# 20180608-iot_eagle7.net
KiCad netlist of a schematic drawn in EAGLE
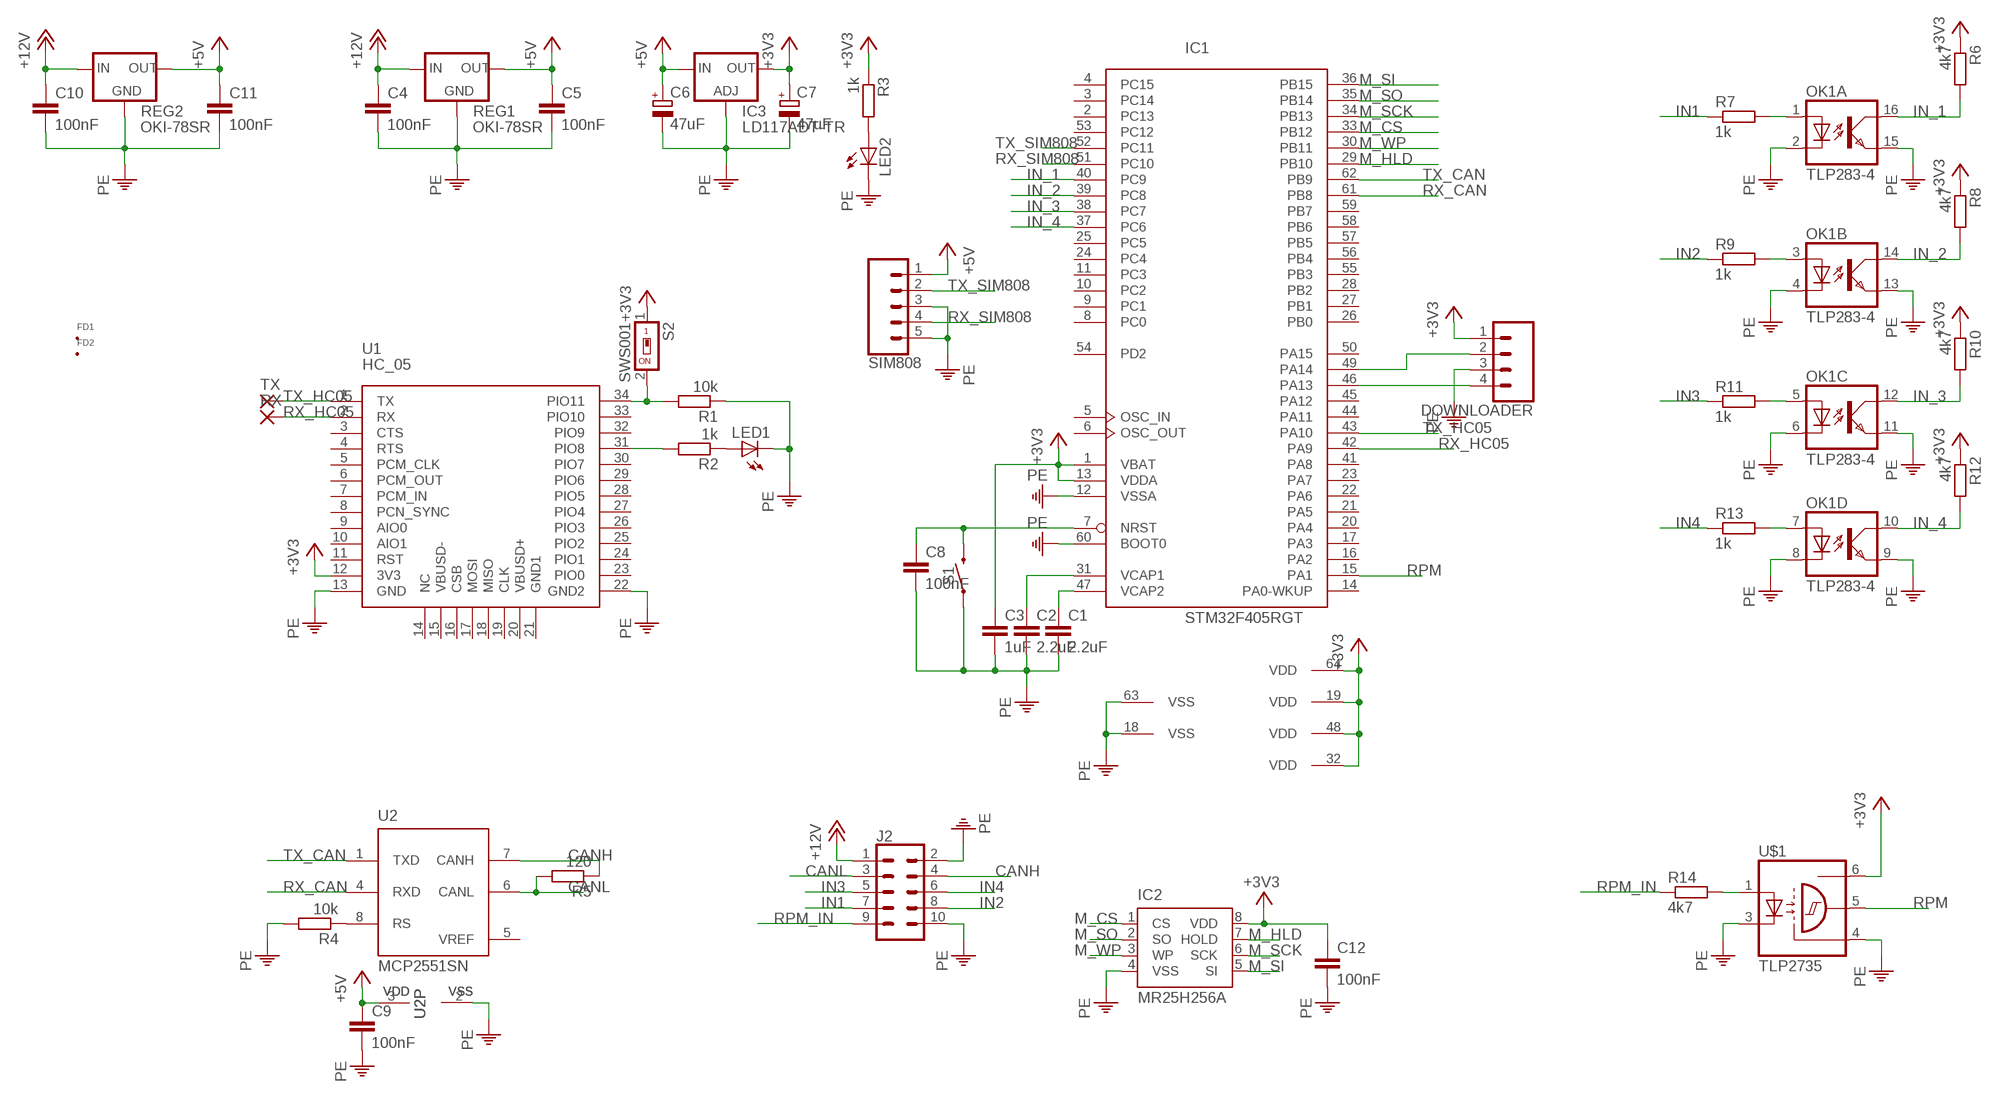
[diagram p0: schematic, sheet 1]

(export (version "E")
  (design (tool "Eeschema 10.0.6"))
  (components
    (comp (ref "C1")
      (value "2.2uF")
      (footprint "eagle-import:C0805")
      (libsource (lib "eagle-import") (part "C-EUC0805"))
    )
    (comp (ref "C2")
      (value "2.2uF")
      (footprint "eagle-import:C0805")
      (libsource (lib "eagle-import") (part "C-EUC0805"))
    )
    (comp (ref "C3")
      (value "1uF")
      (footprint "eagle-import:C0805")
      (libsource (lib "eagle-import") (part "C-EUC0805"))
    )
    (comp (ref "C4")
      (value "100nF")
      (footprint "eagle-import:C0805")
      (libsource (lib "eagle-import") (part "C-EUC0805"))
    )
    (comp (ref "C5")
      (value "100nF")
      (footprint "eagle-import:C0805")
      (libsource (lib "eagle-import") (part "C-EUC0805"))
    )
    (comp (ref "C6")
      (value "47uF")
      (footprint "eagle-import:CT7343")
      (libsource (lib "eagle-import") (part "CPOL-EUCT7343"))
    )
    (comp (ref "C7")
      (value "47uF")
      (footprint "eagle-import:CT7343")
      (libsource (lib "eagle-import") (part "CPOL-EUCT7343"))
    )
    (comp (ref "C8")
      (value "100nF")
      (footprint "eagle-import:C0805")
      (libsource (lib "eagle-import") (part "C-EUC0805"))
    )
    (comp (ref "C9")
      (value "100nF")
      (footprint "eagle-import:C0805")
      (libsource (lib "eagle-import") (part "C-EUC0805"))
    )
    (comp (ref "C10")
      (value "100nF")
      (footprint "eagle-import:C0805")
      (libsource (lib "eagle-import") (part "C-EUC0805"))
    )
    (comp (ref "C11")
      (value "100nF")
      (footprint "eagle-import:C0805")
      (libsource (lib "eagle-import") (part "C-EUC0805"))
    )
    (comp (ref "C12")
      (value "100nF")
      (footprint "eagle-import:C0805")
      (libsource (lib "eagle-import") (part "C-EUC0805"))
    )
    (comp (ref "DOWNLOADER")
      (value "CONN_04")
      (footprint "eagle-import:1X04")
      (libsource (lib "eagle-import") (part "CONN_04"))
    )
    (comp (ref "FD1")
      (value "FID_40MIL")
      (footprint "eagle-import:FID_040")
      (libsource (lib "eagle-import") (part "FID_40MIL"))
    )
    (comp (ref "FD2")
      (value "FID_40MIL")
      (footprint "eagle-import:FID_040")
      (libsource (lib "eagle-import") (part "FID_40MIL"))
    )
    (comp (ref "IC1")
      (value "STM32F405RGT")
      (footprint "eagle-import:LQFP64")
      (fields (field (name "SPICEPREFIX") "X"))
      (libsource (lib "eagle-import") (part "STM32F405RTG"))
    )
    (comp (ref "IC2")
      (value "MR25H256A")
      (footprint "eagle-import:SON127P600X500X90-9T210")
      (libsource (lib "eagle-import") (part "MR25H256A"))
    )
    (comp (ref "IC3")
      (value "LD117ADT-TR")
      (footprint "eagle-import:DPACK")
      (libsource (lib "eagle-import") (part "LD117A?DT-TR"))
    )
    (comp (ref "J2")
      (value "CONN_05X2")
      (footprint "eagle-import:2X5-EDGE_SMD")
      (libsource (lib "eagle-import") (part "CONN_05X2"))
    )
    (comp (ref "LED1")
      (value "LEDCHIP-LED0805")
      (footprint "eagle-import:CHIP-LED0805")
      (libsource (lib "eagle-import") (part "LEDCHIP-LED0805"))
    )
    (comp (ref "LED2")
      (value "LEDCHIP-LED0805")
      (footprint "eagle-import:CHIP-LED0805")
      (libsource (lib "eagle-import") (part "LEDCHIP-LED0805"))
    )
    (comp (ref "OK1")
      (value "TLP283-4")
      (footprint "eagle-import:MINI-FLAT-16")
      (libsource (lib "eagle-import") (part "TLP283-4"))
    )
    (comp (ref "R1")
      (value "10k")
      (footprint "eagle-import:R0805")
      (libsource (lib "eagle-import") (part "R-EU_R0805"))
    )
    (comp (ref "R2")
      (value "1k")
      (footprint "eagle-import:R0805")
      (libsource (lib "eagle-import") (part "R-EU_R0805"))
    )
    (comp (ref "R3")
      (value "1k")
      (footprint "eagle-import:R0805")
      (libsource (lib "eagle-import") (part "R-EU_R0805"))
    )
    (comp (ref "R4")
      (value "10k")
      (footprint "eagle-import:R0805")
      (libsource (lib "eagle-import") (part "R-EU_R0805"))
    )
    (comp (ref "R5")
      (value "120")
      (footprint "eagle-import:R0805")
      (libsource (lib "eagle-import") (part "R-EU_R0805"))
    )
    (comp (ref "R6")
      (value "4k7")
      (footprint "eagle-import:R0805")
      (libsource (lib "eagle-import") (part "R-EU_R0805"))
    )
    (comp (ref "R7")
      (value "1k")
      (footprint "eagle-import:R0805")
      (libsource (lib "eagle-import") (part "R-EU_R0805"))
    )
    (comp (ref "R8")
      (value "4k7")
      (footprint "eagle-import:R0805")
      (libsource (lib "eagle-import") (part "R-EU_R0805"))
    )
    (comp (ref "R9")
      (value "1k")
      (footprint "eagle-import:R0805")
      (libsource (lib "eagle-import") (part "R-EU_R0805"))
    )
    (comp (ref "R10")
      (value "4k7")
      (footprint "eagle-import:R0805")
      (libsource (lib "eagle-import") (part "R-EU_R0805"))
    )
    (comp (ref "R11")
      (value "1k")
      (footprint "eagle-import:R0805")
      (libsource (lib "eagle-import") (part "R-EU_R0805"))
    )
    (comp (ref "R12")
      (value "4k7")
      (footprint "eagle-import:R0805")
      (libsource (lib "eagle-import") (part "R-EU_R0805"))
    )
    (comp (ref "R13")
      (value "1k")
      (footprint "eagle-import:R0805")
      (libsource (lib "eagle-import") (part "R-EU_R0805"))
    )
    (comp (ref "R14")
      (value "4k7")
      (footprint "eagle-import:R0805")
      (libsource (lib "eagle-import") (part "R-EU_R0805"))
    )
    (comp (ref "REG1")
      (value "OKI-78SR")
      (footprint "eagle-import:HDRV3W64P254_1X3_1195X508X838B")
      (libsource (lib "eagle-import") (part "OKI-78SR"))
    )
    (comp (ref "REG2")
      (value "OKI-78SR")
      (footprint "eagle-import:HDRV3W64P254_1X3_1195X508X838B")
      (libsource (lib "eagle-import") (part "OKI-78SR"))
    )
    (comp (ref "RX")
      (value "SMD2")
      (footprint "eagle-import:SMD1,27-2,54")
      (libsource (lib "eagle-import") (part "SMD2"))
    )
    (comp (ref "S1")
      (value "MOMENTARY-SWITCH-SPST-SMD-6.0X3.5MM")
      (footprint "eagle-import:TACTILE_SWITCH_SMD_6.0X3.5MM")
      (libsource (lib "eagle-import") (part "MOMENTARY-SWITCH-SPST-SMD-6.0X3.5MM"))
    )
    (comp (ref "S2")
      (value "SWS001")
      (footprint "eagle-import:SMS-001")
      (libsource (lib "eagle-import") (part "SWS001"))
    )
    (comp (ref "SIM808")
      (value "CONN_05")
      (footprint "eagle-import:1X05")
      (libsource (lib "eagle-import") (part "CONN_05"))
    )
    (comp (ref "TX")
      (value "SMD2")
      (footprint "eagle-import:SMD1,27-2,54")
      (libsource (lib "eagle-import") (part "SMD2"))
    )
    (comp (ref "U$1")
      (value "TLP2735")
      (footprint "eagle-import:SOIC127P1000X210-6")
      (libsource (lib "eagle-import") (part "TLP2735"))
    )
    (comp (ref "U1")
      (value "HC_05")
      (footprint "eagle-import:BLUETOOTH_SMD")
      (libsource (lib "eagle-import") (part "HC_05"))
    )
    (comp (ref "U2")
      (value "MCP2551SN")
      (footprint "eagle-import:SO-08")
      (fields (field (name "SPICEPREFIX") "X"))
      (libsource (lib "eagle-import") (part "MCP2551SN"))
    )
  )
  (nets
    (net (code "1") (name "+3V3") (class "Default")
      (node (ref "C12") (pin "1") (pinfunction "1_1") (pintype "passive"))
      (node (ref "C3") (pin "1") (pinfunction "1_1") (pintype "passive"))
      (node (ref "C7") (pin "+") (pinfunction "+_+") (pintype "passive"))
      (node (ref "DOWNLOADER") (pin "1") (pinfunction "1_1") (pintype "passive"))
      (node (ref "IC1") (pin "1") (pinfunction "VBAT_1") (pintype "power_in"))
      (node (ref "IC1") (pin "13") (pinfunction "VDDA_13") (pintype "power_in"))
      (node (ref "IC1") (pin "19") (pinfunction "VDD_19") (pintype "power_in"))
      (node (ref "IC1") (pin "32") (pinfunction "VDD_32") (pintype "power_in"))
      (node (ref "IC1") (pin "48") (pinfunction "VDD_48") (pintype "power_in"))
      (node (ref "IC1") (pin "64") (pinfunction "VDD_64") (pintype "power_in"))
      (node (ref "IC2") (pin "8") (pinfunction "VDD_8") (pintype "power_in"))
      (node (ref "IC3") (pin "4") (pinfunction "OUT_4") (pintype "passive"))
      (node (ref "R10") (pin "1") (pinfunction "1_1") (pintype "passive"))
      (node (ref "R12") (pin "1") (pinfunction "1_1") (pintype "passive"))
      (node (ref "R3") (pin "1") (pinfunction "1_1") (pintype "passive"))
      (node (ref "R6") (pin "1") (pinfunction "1_1") (pintype "passive"))
      (node (ref "R8") (pin "1") (pinfunction "1_1") (pintype "passive"))
      (node (ref "S2") (pin "1") (pinfunction "1_1") (pintype "passive"))
      (node (ref "U$1") (pin "6") (pinfunction "VCC_6") (pintype "passive"))
      (node (ref "U1") (pin "12") (pinfunction "3V3_12") (pintype "bidirectional"))
    )
    (net (code "2") (name "+5V") (class "Default")
      (node (ref "C11") (pin "1") (pinfunction "1_1") (pintype "passive"))
      (node (ref "C5") (pin "1") (pinfunction "1_1") (pintype "passive"))
      (node (ref "C6") (pin "+") (pinfunction "+_+") (pintype "passive"))
      (node (ref "C9") (pin "1") (pinfunction "1_1") (pintype "passive"))
      (node (ref "IC3") (pin "3") (pinfunction "IN_3") (pintype "input"))
      (node (ref "REG1") (pin "3") (pinfunction "OUT_3") (pintype "passive"))
      (node (ref "REG2") (pin "3") (pinfunction "OUT_3") (pintype "passive"))
      (node (ref "SIM808") (pin "1") (pinfunction "1_1") (pintype "passive"))
      (node (ref "U2") (pin "3") (pinfunction "VDD_3") (pintype "power_in"))
    )
    (net (code "3") (name "+12V") (class "Default")
      (node (ref "C10") (pin "1") (pinfunction "1_1") (pintype "passive"))
      (node (ref "C4") (pin "1") (pinfunction "1_1") (pintype "passive"))
      (node (ref "J2") (pin "1") (pinfunction "1_1") (pintype "passive"))
      (node (ref "REG1") (pin "1") (pinfunction "IN_1") (pintype "input"))
      (node (ref "REG2") (pin "1") (pinfunction "IN_1") (pintype "input"))
    )
    (net (code "4") (name "/CANH") (class "Default")
      (node (ref "J2") (pin "4") (pinfunction "4_4") (pintype "passive"))
      (node (ref "R5") (pin "1") (pinfunction "1_1") (pintype "passive"))
      (node (ref "U2") (pin "7") (pinfunction "CANH_7") (pintype "bidirectional"))
    )
    (net (code "5") (name "/CANL") (class "Default")
      (node (ref "J2") (pin "3") (pinfunction "3_3") (pintype "passive"))
      (node (ref "R5") (pin "2") (pinfunction "2_2") (pintype "passive"))
      (node (ref "U2") (pin "6") (pinfunction "CANL_6") (pintype "bidirectional"))
    )
    (net (code "6") (name "/IN1") (class "Default")
      (node (ref "J2") (pin "7") (pinfunction "7_7") (pintype "passive"))
      (node (ref "R7") (pin "1") (pinfunction "1_1") (pintype "passive"))
    )
    (net (code "7") (name "/IN2") (class "Default")
      (node (ref "J2") (pin "8") (pinfunction "8_8") (pintype "passive"))
      (node (ref "R9") (pin "1") (pinfunction "1_1") (pintype "passive"))
    )
    (net (code "8") (name "/IN3") (class "Default")
      (node (ref "J2") (pin "5") (pinfunction "5_5") (pintype "passive"))
      (node (ref "R11") (pin "1") (pinfunction "1_1") (pintype "passive"))
    )
    (net (code "9") (name "/IN4") (class "Default")
      (node (ref "J2") (pin "6") (pinfunction "6_6") (pintype "passive"))
      (node (ref "R13") (pin "1") (pinfunction "1_1") (pintype "passive"))
    )
    (net (code "10") (name "/IN_1") (class "Default")
      (node (ref "IC1") (pin "40") (pinfunction "PC9_40") (pintype "bidirectional"))
      (node (ref "OK1") (pin "16") (pinfunction "COL_16") (pintype "passive"))
      (node (ref "R6") (pin "2") (pinfunction "2_2") (pintype "passive"))
    )
    (net (code "11") (name "/IN_2") (class "Default")
      (node (ref "IC1") (pin "39") (pinfunction "PC8_39") (pintype "bidirectional"))
      (node (ref "OK1") (pin "14") (pinfunction "COL_14") (pintype "passive"))
      (node (ref "R8") (pin "2") (pinfunction "2_2") (pintype "passive"))
    )
    (net (code "12") (name "/IN_3") (class "Default")
      (node (ref "IC1") (pin "38") (pinfunction "PC7_38") (pintype "bidirectional"))
      (node (ref "OK1") (pin "12") (pinfunction "COL_12") (pintype "passive"))
      (node (ref "R10") (pin "2") (pinfunction "2_2") (pintype "passive"))
    )
    (net (code "13") (name "/IN_4") (class "Default")
      (node (ref "IC1") (pin "37") (pinfunction "PC6_37") (pintype "bidirectional"))
      (node (ref "OK1") (pin "10") (pinfunction "COL_10") (pintype "passive"))
      (node (ref "R12") (pin "2") (pinfunction "2_2") (pintype "passive"))
    )
    (net (code "14") (name "/M_CS") (class "Default")
      (node (ref "IC1") (pin "33") (pinfunction "PB12_33") (pintype "bidirectional"))
      (node (ref "IC2") (pin "1") (pinfunction "CS_1") (pintype "bidirectional"))
    )
    (net (code "15") (name "/M_HLD") (class "Default")
      (node (ref "IC1") (pin "29") (pinfunction "PB10_29") (pintype "bidirectional"))
      (node (ref "IC2") (pin "7") (pinfunction "HOLD_7") (pintype "output"))
    )
    (net (code "16") (name "/M_SCK") (class "Default")
      (node (ref "IC1") (pin "34") (pinfunction "PB13_34") (pintype "bidirectional"))
      (node (ref "IC2") (pin "6") (pinfunction "SCK_6") (pintype "power_in"))
    )
    (net (code "17") (name "/M_SI") (class "Default")
      (node (ref "IC1") (pin "36") (pinfunction "PB15_36") (pintype "bidirectional"))
      (node (ref "IC2") (pin "5") (pinfunction "SI_5") (pintype "input"))
    )
    (net (code "18") (name "/M_SO") (class "Default")
      (node (ref "IC1") (pin "35") (pinfunction "PB14_35") (pintype "bidirectional"))
      (node (ref "IC2") (pin "2") (pinfunction "SO_2") (pintype "input"))
    )
    (net (code "19") (name "/M_WP") (class "Default")
      (node (ref "IC1") (pin "30") (pinfunction "PB11_30") (pintype "bidirectional"))
      (node (ref "IC2") (pin "3") (pinfunction "WP_3") (pintype "input"))
    )
    (net (code "20") (name "/RPM") (class "Default")
      (node (ref "IC1") (pin "15") (pinfunction "PA1_15") (pintype "bidirectional"))
      (node (ref "U$1") (pin "5") (pinfunction "OUT_5") (pintype "passive"))
    )
    (net (code "21") (name "/RPM_IN") (class "Default")
      (node (ref "J2") (pin "9") (pinfunction "9_9") (pintype "passive"))
      (node (ref "R14") (pin "1") (pinfunction "1_1") (pintype "passive"))
    )
    (net (code "22") (name "/RX_CAN") (class "Default")
      (node (ref "IC1") (pin "61") (pinfunction "PB8_61") (pintype "bidirectional"))
      (node (ref "U2") (pin "4") (pinfunction "RXD_4") (pintype "output"))
    )
    (net (code "23") (name "/RX_HC05") (class "Default")
      (node (ref "IC1") (pin "42") (pinfunction "PA9_42") (pintype "bidirectional"))
      (node (ref "RX") (pin "1") (pinfunction "P_1") (pintype "passive"))
      (node (ref "U1") (pin "2") (pinfunction "RX_2") (pintype "bidirectional"))
    )
    (net (code "24") (name "/RX_SIM808") (class "Default")
      (node (ref "IC1") (pin "51") (pinfunction "PC10_51") (pintype "bidirectional"))
      (node (ref "SIM808") (pin "4") (pinfunction "4_4") (pintype "passive"))
    )
    (net (code "25") (name "/TX_CAN") (class "Default")
      (node (ref "IC1") (pin "62") (pinfunction "PB9_62") (pintype "bidirectional"))
      (node (ref "U2") (pin "1") (pinfunction "TXD_1") (pintype "input"))
    )
    (net (code "26") (name "/TX_HC05") (class "Default")
      (node (ref "IC1") (pin "43") (pinfunction "PA10_43") (pintype "bidirectional"))
      (node (ref "TX") (pin "1") (pinfunction "P_1") (pintype "passive"))
      (node (ref "U1") (pin "1") (pinfunction "TX_1") (pintype "bidirectional"))
    )
    (net (code "27") (name "/TX_SIM808") (class "Default")
      (node (ref "IC1") (pin "52") (pinfunction "PC11_52") (pintype "bidirectional"))
      (node (ref "SIM808") (pin "2") (pinfunction "2_2") (pintype "passive"))
    )
    (net (code "28") (name "/VREF") (class "Default")
      (node (ref "U2") (pin "5") (pinfunction "VREF_5") (pintype "power_in"))
    )
    (net (code "29") (name "Net-(IC1A-NRST)") (class "Default")
      (node (ref "C8") (pin "1") (pinfunction "1_1") (pintype "passive"))
      (node (ref "IC1") (pin "7") (pinfunction "NRST_7") (pintype "bidirectional"))
      (node (ref "S1") (pin "2") (pinfunction "2_2") (pintype "passive"))
    )
    (net (code "30") (name "Net-(IC1A-PA13)") (class "Default")
      (node (ref "DOWNLOADER") (pin "4") (pinfunction "4_4") (pintype "passive"))
      (node (ref "IC1") (pin "46") (pinfunction "PA13_46") (pintype "bidirectional"))
    )
    (net (code "31") (name "Net-(IC1A-PA14)") (class "Default")
      (node (ref "DOWNLOADER") (pin "2") (pinfunction "2_2") (pintype "passive"))
      (node (ref "IC1") (pin "49") (pinfunction "PA14_49") (pintype "bidirectional"))
    )
    (net (code "32") (name "Net-(IC1A-VCAP1)") (class "Default")
      (node (ref "C2") (pin "1") (pinfunction "1_1") (pintype "passive"))
      (node (ref "IC1") (pin "31") (pinfunction "VCAP1_31") (pintype "power_in"))
    )
    (net (code "33") (name "Net-(IC1A-VCAP2)") (class "Default")
      (node (ref "C1") (pin "1") (pinfunction "1_1") (pintype "passive"))
      (node (ref "IC1") (pin "47") (pinfunction "VCAP2_47") (pintype "power_in"))
    )
    (net (code "34") (name "Net-(LED1-PadA)") (class "Default")
      (node (ref "LED1") (pin "A") (pinfunction "A_A") (pintype "passive"))
      (node (ref "R2") (pin "1") (pinfunction "1_1") (pintype "passive"))
    )
    (net (code "35") (name "Net-(LED2-PadA)") (class "Default")
      (node (ref "LED2") (pin "A") (pinfunction "A_A") (pintype "passive"))
      (node (ref "R3") (pin "2") (pinfunction "2_2") (pintype "passive"))
    )
    (net (code "36") (name "Net-(OK1A-A)") (class "Default")
      (node (ref "OK1") (pin "1") (pinfunction "A_1") (pintype "passive"))
      (node (ref "R7") (pin "2") (pinfunction "2_2") (pintype "passive"))
    )
    (net (code "37") (name "Net-(OK1B-A)") (class "Default")
      (node (ref "OK1") (pin "3") (pinfunction "A_3") (pintype "passive"))
      (node (ref "R9") (pin "2") (pinfunction "2_2") (pintype "passive"))
    )
    (net (code "38") (name "Net-(OK1C-A)") (class "Default")
      (node (ref "OK1") (pin "5") (pinfunction "A_5") (pintype "passive"))
      (node (ref "R11") (pin "2") (pinfunction "2_2") (pintype "passive"))
    )
    (net (code "39") (name "Net-(OK1D-A)") (class "Default")
      (node (ref "OK1") (pin "7") (pinfunction "A_7") (pintype "passive"))
      (node (ref "R13") (pin "2") (pinfunction "2_2") (pintype "passive"))
    )
    (net (code "40") (name "Net-(U$1-A)") (class "Default")
      (node (ref "R14") (pin "2") (pinfunction "2_2") (pintype "passive"))
      (node (ref "U$1") (pin "1") (pinfunction "A_1") (pintype "passive"))
    )
    (net (code "41") (name "Net-(U1-PIO8)") (class "Default")
      (node (ref "R2") (pin "2") (pinfunction "2_2") (pintype "passive"))
      (node (ref "U1") (pin "31") (pinfunction "PIO8_31") (pintype "bidirectional"))
    )
    (net (code "42") (name "Net-(U1-PIO11)") (class "Default")
      (node (ref "R1") (pin "2") (pinfunction "2_2") (pintype "passive"))
      (node (ref "S2") (pin "2") (pinfunction "2_2") (pintype "passive"))
      (node (ref "U1") (pin "34") (pinfunction "PIO11_34") (pintype "bidirectional"))
    )
    (net (code "43") (name "Net-(U2A-RS)") (class "Default")
      (node (ref "R4") (pin "1") (pinfunction "1_1") (pintype "passive"))
      (node (ref "U2") (pin "8") (pinfunction "RS_8") (pintype "input"))
    )
    (net (code "44") (name "PE") (class "Default")
      (node (ref "C1") (pin "2") (pinfunction "2_2") (pintype "passive"))
      (node (ref "C10") (pin "2") (pinfunction "2_2") (pintype "passive"))
      (node (ref "C11") (pin "2") (pinfunction "2_2") (pintype "passive"))
      (node (ref "C12") (pin "2") (pinfunction "2_2") (pintype "passive"))
      (node (ref "C2") (pin "2") (pinfunction "2_2") (pintype "passive"))
      (node (ref "C3") (pin "2") (pinfunction "2_2") (pintype "passive"))
      (node (ref "C4") (pin "2") (pinfunction "2_2") (pintype "passive"))
      (node (ref "C5") (pin "2") (pinfunction "2_2") (pintype "passive"))
      (node (ref "C6") (pin "-") (pinfunction "-_-") (pintype "passive"))
      (node (ref "C7") (pin "-") (pinfunction "-_-") (pintype "passive"))
      (node (ref "C8") (pin "2") (pinfunction "2_2") (pintype "passive"))
      (node (ref "C9") (pin "2") (pinfunction "2_2") (pintype "passive"))
      (node (ref "DOWNLOADER") (pin "3") (pinfunction "3_3") (pintype "passive"))
      (node (ref "IC1") (pin "12") (pinfunction "VSSA_12") (pintype "power_in"))
      (node (ref "IC1") (pin "18") (pinfunction "VSS_18") (pintype "power_in"))
      (node (ref "IC1") (pin "60") (pinfunction "BOOT0_60") (pintype "input"))
      (node (ref "IC1") (pin "63") (pinfunction "VSS_63") (pintype "power_in"))
      (node (ref "IC2") (pin "4") (pinfunction "VSS_4") (pintype "input"))
      (node (ref "IC3") (pin "1") (pinfunction "ADJ_1") (pintype "input"))
      (node (ref "J2") (pin "10") (pinfunction "10_10") (pintype "passive"))
      (node (ref "J2") (pin "2") (pinfunction "2_2") (pintype "passive"))
      (node (ref "LED1") (pin "C") (pinfunction "C_C") (pintype "passive"))
      (node (ref "LED2") (pin "C") (pinfunction "C_C") (pintype "passive"))
      (node (ref "OK1") (pin "11") (pinfunction "EMIT_11") (pintype "passive"))
      (node (ref "OK1") (pin "13") (pinfunction "EMIT_13") (pintype "passive"))
      (node (ref "OK1") (pin "15") (pinfunction "EMIT_15") (pintype "passive"))
      (node (ref "OK1") (pin "2") (pinfunction "C_2") (pintype "passive"))
      (node (ref "OK1") (pin "4") (pinfunction "C_4") (pintype "passive"))
      (node (ref "OK1") (pin "6") (pinfunction "C_6") (pintype "passive"))
      (node (ref "OK1") (pin "8") (pinfunction "C_8") (pintype "passive"))
      (node (ref "OK1") (pin "9") (pinfunction "EMIT_9") (pintype "passive"))
      (node (ref "R1") (pin "1") (pinfunction "1_1") (pintype "passive"))
      (node (ref "R4") (pin "2") (pinfunction "2_2") (pintype "passive"))
      (node (ref "REG1") (pin "2") (pinfunction "GND_2") (pintype "input"))
      (node (ref "REG2") (pin "2") (pinfunction "GND_2") (pintype "input"))
      (node (ref "S1") (pin "1") (pinfunction "1_1") (pintype "passive"))
      (node (ref "SIM808") (pin "3") (pinfunction "3_3") (pintype "passive"))
      (node (ref "SIM808") (pin "5") (pinfunction "5_5") (pintype "passive"))
      (node (ref "U$1") (pin "3") (pinfunction "C_3") (pintype "passive"))
      (node (ref "U$1") (pin "4") (pinfunction "GND_4") (pintype "passive"))
      (node (ref "U1") (pin "13") (pinfunction "GND_13") (pintype "bidirectional"))
      (node (ref "U1") (pin "22") (pinfunction "GND2_22") (pintype "bidirectional"))
      (node (ref "U2") (pin "2") (pinfunction "VSS_2") (pintype "power_in"))
    )
    (net (code "45") (name "unconnected-(IC1A-OSC_IN-Pad5)") (class "Default")
      (node (ref "IC1") (pin "5") (pinfunction "OSC_IN_5") (pintype "bidirectional"))
    )
    (net (code "46") (name "unconnected-(IC1A-OSC_OUT-Pad6)") (class "Default")
      (node (ref "IC1") (pin "6") (pinfunction "OSC_OUT_6") (pintype "bidirectional"))
    )
    (net (code "47") (name "unconnected-(IC1A-PA0-WKUP-Pad14)") (class "Default")
      (node (ref "IC1") (pin "14") (pinfunction "PA0-WKUP_14") (pintype "bidirectional"))
    )
    (net (code "48") (name "unconnected-(IC1A-PA2-Pad16)") (class "Default")
      (node (ref "IC1") (pin "16") (pinfunction "PA2_16") (pintype "bidirectional"))
    )
    (net (code "49") (name "unconnected-(IC1A-PA3-Pad17)") (class "Default")
      (node (ref "IC1") (pin "17") (pinfunction "PA3_17") (pintype "bidirectional"))
    )
    (net (code "50") (name "unconnected-(IC1A-PA4-Pad20)") (class "Default")
      (node (ref "IC1") (pin "20") (pinfunction "PA4_20") (pintype "bidirectional"))
    )
    (net (code "51") (name "unconnected-(IC1A-PA5-Pad21)") (class "Default")
      (node (ref "IC1") (pin "21") (pinfunction "PA5_21") (pintype "bidirectional"))
    )
    (net (code "52") (name "unconnected-(IC1A-PA6-Pad22)") (class "Default")
      (node (ref "IC1") (pin "22") (pinfunction "PA6_22") (pintype "bidirectional"))
    )
    (net (code "53") (name "unconnected-(IC1A-PA7-Pad23)") (class "Default")
      (node (ref "IC1") (pin "23") (pinfunction "PA7_23") (pintype "bidirectional"))
    )
    (net (code "54") (name "unconnected-(IC1A-PA8-Pad41)") (class "Default")
      (node (ref "IC1") (pin "41") (pinfunction "PA8_41") (pintype "bidirectional"))
    )
    (net (code "55") (name "unconnected-(IC1A-PA11-Pad44)") (class "Default")
      (node (ref "IC1") (pin "44") (pinfunction "PA11_44") (pintype "bidirectional"))
    )
    (net (code "56") (name "unconnected-(IC1A-PA12-Pad45)") (class "Default")
      (node (ref "IC1") (pin "45") (pinfunction "PA12_45") (pintype "bidirectional"))
    )
    (net (code "57") (name "unconnected-(IC1A-PA15-Pad50)") (class "Default")
      (node (ref "IC1") (pin "50") (pinfunction "PA15_50") (pintype "bidirectional"))
    )
    (net (code "58") (name "unconnected-(IC1A-PB0-Pad26)") (class "Default")
      (node (ref "IC1") (pin "26") (pinfunction "PB0_26") (pintype "bidirectional"))
    )
    (net (code "59") (name "unconnected-(IC1A-PB1-Pad27)") (class "Default")
      (node (ref "IC1") (pin "27") (pinfunction "PB1_27") (pintype "bidirectional"))
    )
    (net (code "60") (name "unconnected-(IC1A-PB2-Pad28)") (class "Default")
      (node (ref "IC1") (pin "28") (pinfunction "PB2_28") (pintype "bidirectional"))
    )
    (net (code "61") (name "unconnected-(IC1A-PB3-Pad55)") (class "Default")
      (node (ref "IC1") (pin "55") (pinfunction "PB3_55") (pintype "bidirectional"))
    )
    (net (code "62") (name "unconnected-(IC1A-PB4-Pad56)") (class "Default")
      (node (ref "IC1") (pin "56") (pinfunction "PB4_56") (pintype "bidirectional"))
    )
    (net (code "63") (name "unconnected-(IC1A-PB5-Pad57)") (class "Default")
      (node (ref "IC1") (pin "57") (pinfunction "PB5_57") (pintype "bidirectional"))
    )
    (net (code "64") (name "unconnected-(IC1A-PB6-Pad58)") (class "Default")
      (node (ref "IC1") (pin "58") (pinfunction "PB6_58") (pintype "bidirectional"))
    )
    (net (code "65") (name "unconnected-(IC1A-PB7-Pad59)") (class "Default")
      (node (ref "IC1") (pin "59") (pinfunction "PB7_59") (pintype "bidirectional"))
    )
    (net (code "66") (name "unconnected-(IC1A-PC0-Pad8)") (class "Default")
      (node (ref "IC1") (pin "8") (pinfunction "PC0_8") (pintype "bidirectional"))
    )
    (net (code "67") (name "unconnected-(IC1A-PC1-Pad9)") (class "Default")
      (node (ref "IC1") (pin "9") (pinfunction "PC1_9") (pintype "bidirectional"))
    )
    (net (code "68") (name "unconnected-(IC1A-PC2-Pad10)") (class "Default")
      (node (ref "IC1") (pin "10") (pinfunction "PC2_10") (pintype "bidirectional"))
    )
    (net (code "69") (name "unconnected-(IC1A-PC3-Pad11)") (class "Default")
      (node (ref "IC1") (pin "11") (pinfunction "PC3_11") (pintype "bidirectional"))
    )
    (net (code "70") (name "unconnected-(IC1A-PC4-Pad24)") (class "Default")
      (node (ref "IC1") (pin "24") (pinfunction "PC4_24") (pintype "bidirectional"))
    )
    (net (code "71") (name "unconnected-(IC1A-PC5-Pad25)") (class "Default")
      (node (ref "IC1") (pin "25") (pinfunction "PC5_25") (pintype "bidirectional"))
    )
    (net (code "72") (name "unconnected-(IC1A-PC12-Pad53)") (class "Default")
      (node (ref "IC1") (pin "53") (pinfunction "PC12_53") (pintype "bidirectional"))
    )
    (net (code "73") (name "unconnected-(IC1A-PC13-Pad2)") (class "Default")
      (node (ref "IC1") (pin "2") (pinfunction "PC13_2") (pintype "bidirectional"))
    )
    (net (code "74") (name "unconnected-(IC1A-PC14-Pad3)") (class "Default")
      (node (ref "IC1") (pin "3") (pinfunction "PC14_3") (pintype "bidirectional"))
    )
    (net (code "75") (name "unconnected-(IC1A-PC15-Pad4)") (class "Default")
      (node (ref "IC1") (pin "4") (pinfunction "PC15_4") (pintype "bidirectional"))
    )
    (net (code "76") (name "unconnected-(IC1A-PD2-Pad54)") (class "Default")
      (node (ref "IC1") (pin "54") (pinfunction "PD2_54") (pintype "bidirectional"))
    )
    (net (code "77") (name "unconnected-(U1-AIO0-Pad9)") (class "Default")
      (node (ref "U1") (pin "9") (pinfunction "AIO0_9") (pintype "bidirectional"))
    )
    (net (code "78") (name "unconnected-(U1-AIO1-Pad10)") (class "Default")
      (node (ref "U1") (pin "10") (pinfunction "AIO1_10") (pintype "bidirectional"))
    )
    (net (code "79") (name "unconnected-(U1-CLK-Pad19)") (class "Default")
      (node (ref "U1") (pin "19") (pinfunction "CLK_19") (pintype "bidirectional"))
    )
    (net (code "80") (name "unconnected-(U1-CSB-Pad16)") (class "Default")
      (node (ref "U1") (pin "16") (pinfunction "CSB_16") (pintype "bidirectional"))
    )
    (net (code "81") (name "unconnected-(U1-CTS-Pad3)") (class "Default")
      (node (ref "U1") (pin "3") (pinfunction "CTS_3") (pintype "bidirectional"))
    )
    (net (code "82") (name "unconnected-(U1-GND1-Pad21)") (class "Default")
      (node (ref "U1") (pin "21") (pinfunction "GND1_21") (pintype "bidirectional"))
    )
    (net (code "83") (name "unconnected-(U1-MISO-Pad18)") (class "Default")
      (node (ref "U1") (pin "18") (pinfunction "MISO_18") (pintype "bidirectional"))
    )
    (net (code "84") (name "unconnected-(U1-MOSI-Pad17)") (class "Default")
      (node (ref "U1") (pin "17") (pinfunction "MOSI_17") (pintype "bidirectional"))
    )
    (net (code "85") (name "unconnected-(U1-NC-Pad14)") (class "Default")
      (node (ref "U1") (pin "14") (pinfunction "NC_14") (pintype "bidirectional"))
    )
    (net (code "86") (name "unconnected-(U1-PCM_CLK-Pad5)") (class "Default")
      (node (ref "U1") (pin "5") (pinfunction "PCM_CLK_5") (pintype "bidirectional"))
    )
    (net (code "87") (name "unconnected-(U1-PCM_IN-Pad7)") (class "Default")
      (node (ref "U1") (pin "7") (pinfunction "PCM_IN_7") (pintype "bidirectional"))
    )
    (net (code "88") (name "unconnected-(U1-PCM_OUT-Pad6)") (class "Default")
      (node (ref "U1") (pin "6") (pinfunction "PCM_OUT_6") (pintype "bidirectional"))
    )
    (net (code "89") (name "unconnected-(U1-PCN_SYNC-Pad8)") (class "Default")
      (node (ref "U1") (pin "8") (pinfunction "PCN_SYNC_8") (pintype "bidirectional"))
    )
    (net (code "90") (name "unconnected-(U1-PIO0-Pad23)") (class "Default")
      (node (ref "U1") (pin "23") (pinfunction "PIO0_23") (pintype "bidirectional"))
    )
    (net (code "91") (name "unconnected-(U1-PIO1-Pad24)") (class "Default")
      (node (ref "U1") (pin "24") (pinfunction "PIO1_24") (pintype "bidirectional"))
    )
    (net (code "92") (name "unconnected-(U1-PIO2-Pad25)") (class "Default")
      (node (ref "U1") (pin "25") (pinfunction "PIO2_25") (pintype "bidirectional"))
    )
    (net (code "93") (name "unconnected-(U1-PIO3-Pad26)") (class "Default")
      (node (ref "U1") (pin "26") (pinfunction "PIO3_26") (pintype "bidirectional"))
    )
    (net (code "94") (name "unconnected-(U1-PIO4-Pad27)") (class "Default")
      (node (ref "U1") (pin "27") (pinfunction "PIO4_27") (pintype "bidirectional"))
    )
    (net (code "95") (name "unconnected-(U1-PIO5-Pad28)") (class "Default")
      (node (ref "U1") (pin "28") (pinfunction "PIO5_28") (pintype "bidirectional"))
    )
    (net (code "96") (name "unconnected-(U1-PIO6-Pad29)") (class "Default")
      (node (ref "U1") (pin "29") (pinfunction "PIO6_29") (pintype "bidirectional"))
    )
    (net (code "97") (name "unconnected-(U1-PIO7-Pad30)") (class "Default")
      (node (ref "U1") (pin "30") (pinfunction "PIO7_30") (pintype "bidirectional"))
    )
    (net (code "98") (name "unconnected-(U1-PIO9-Pad32)") (class "Default")
      (node (ref "U1") (pin "32") (pinfunction "PIO9_32") (pintype "bidirectional"))
    )
    (net (code "99") (name "unconnected-(U1-PIO10-Pad33)") (class "Default")
      (node (ref "U1") (pin "33") (pinfunction "PIO10_33") (pintype "bidirectional"))
    )
    (net (code "100") (name "unconnected-(U1-RST-Pad11)") (class "Default")
      (node (ref "U1") (pin "11") (pinfunction "RST_11") (pintype "bidirectional"))
    )
    (net (code "101") (name "unconnected-(U1-RTS-Pad4)") (class "Default")
      (node (ref "U1") (pin "4") (pinfunction "RTS_4") (pintype "bidirectional"))
    )
    (net (code "102") (name "unconnected-(U1-VBUSD+-Pad20)") (class "Default")
      (node (ref "U1") (pin "20") (pinfunction "VBUSD+_20") (pintype "bidirectional"))
    )
    (net (code "103") (name "unconnected-(U1-VBUSD--Pad15)") (class "Default")
      (node (ref "U1") (pin "15") (pinfunction "VBUSD-_15") (pintype "bidirectional"))
    )
  )
)
